# axiom_beta_plugin_module_1xUSB30.net
KiCad netlist of a schematic drawn in EAGLE
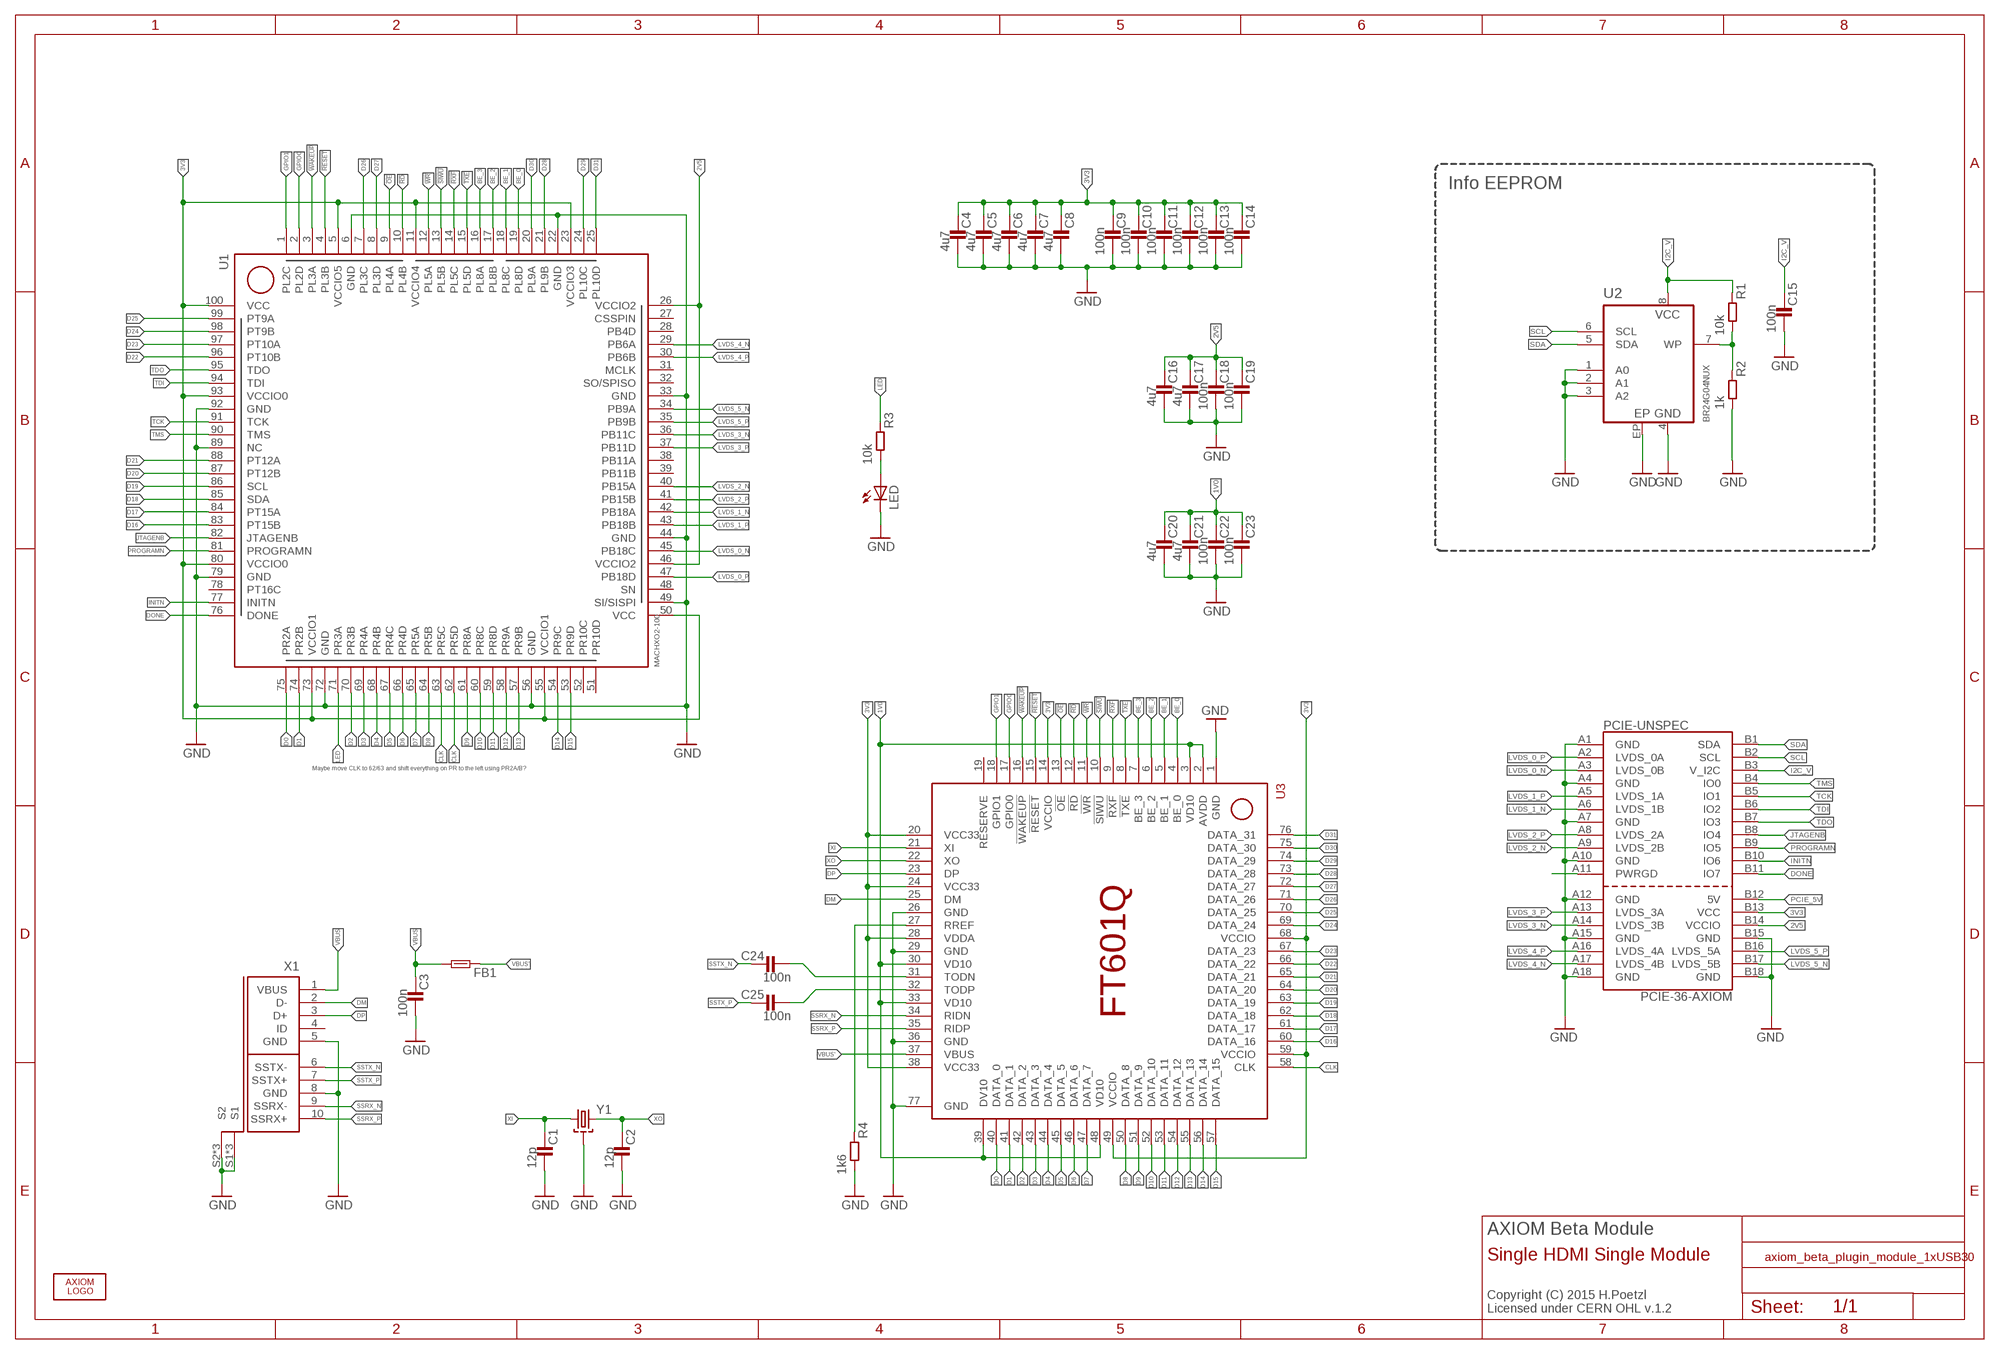
[diagram p0: schematic, sheet 1]

(export (version "E")
  (design (tool "Eeschema 10.0.6"))
  (components
    (comp (ref "C1")
      (value "12p")
      (footprint "eagle-import:0402-C")
      (libsource (lib "eagle-import") (part "C0402-C"))
    )
    (comp (ref "C2")
      (value "12p")
      (footprint "eagle-import:0402-C")
      (libsource (lib "eagle-import") (part "C0402-C"))
    )
    (comp (ref "C3")
      (value "100n")
      (footprint "eagle-import:0402-C")
      (libsource (lib "eagle-import") (part "C0402-C"))
    )
    (comp (ref "C4")
      (value "4u7")
      (footprint "eagle-import:0402-C")
      (libsource (lib "eagle-import") (part "C0402-C"))
    )
    (comp (ref "C5")
      (value "4u7")
      (footprint "eagle-import:0402-C")
      (libsource (lib "eagle-import") (part "C0402-C"))
    )
    (comp (ref "C6")
      (value "4u7")
      (footprint "eagle-import:0402-C")
      (libsource (lib "eagle-import") (part "C0402-C"))
    )
    (comp (ref "C7")
      (value "4u7")
      (footprint "eagle-import:0402-C")
      (libsource (lib "eagle-import") (part "C0402-C"))
    )
    (comp (ref "C8")
      (value "4u7")
      (footprint "eagle-import:0402-C")
      (libsource (lib "eagle-import") (part "C0402-C"))
    )
    (comp (ref "C9")
      (value "100n")
      (footprint "eagle-import:0402-C")
      (libsource (lib "eagle-import") (part "C0402-C"))
    )
    (comp (ref "C10")
      (value "100n")
      (footprint "eagle-import:0402-C")
      (libsource (lib "eagle-import") (part "C0402-C"))
    )
    (comp (ref "C11")
      (value "100n")
      (footprint "eagle-import:0402-C")
      (libsource (lib "eagle-import") (part "C0402-C"))
    )
    (comp (ref "C12")
      (value "100n")
      (footprint "eagle-import:0402-C")
      (libsource (lib "eagle-import") (part "C0402-C"))
    )
    (comp (ref "C13")
      (value "100n")
      (footprint "eagle-import:0402-C")
      (libsource (lib "eagle-import") (part "C0402-C"))
    )
    (comp (ref "C14")
      (value "100n")
      (footprint "eagle-import:0402-C")
      (libsource (lib "eagle-import") (part "C0402-C"))
    )
    (comp (ref "C15")
      (value "100n")
      (footprint "eagle-import:0402-C")
      (libsource (lib "eagle-import") (part "C0402-C"))
    )
    (comp (ref "C16")
      (value "4u7")
      (footprint "eagle-import:0402-C")
      (libsource (lib "eagle-import") (part "C0402-C"))
    )
    (comp (ref "C17")
      (value "4u7")
      (footprint "eagle-import:0402-C")
      (libsource (lib "eagle-import") (part "C0402-C"))
    )
    (comp (ref "C18")
      (value "100n")
      (footprint "eagle-import:0402-C")
      (libsource (lib "eagle-import") (part "C0402-C"))
    )
    (comp (ref "C19")
      (value "100n")
      (footprint "eagle-import:0402-C")
      (libsource (lib "eagle-import") (part "C0402-C"))
    )
    (comp (ref "C20")
      (value "4u7")
      (footprint "eagle-import:0402-C")
      (libsource (lib "eagle-import") (part "C0402-C"))
    )
    (comp (ref "C21")
      (value "4u7")
      (footprint "eagle-import:0402-C")
      (libsource (lib "eagle-import") (part "C0402-C"))
    )
    (comp (ref "C22")
      (value "100n")
      (footprint "eagle-import:0402-C")
      (libsource (lib "eagle-import") (part "C0402-C"))
    )
    (comp (ref "C23")
      (value "100n")
      (footprint "eagle-import:0402-C")
      (libsource (lib "eagle-import") (part "C0402-C"))
    )
    (comp (ref "C24")
      (value "100n")
      (footprint "eagle-import:0201-C")
      (libsource (lib "eagle-import") (part "C0201-C"))
    )
    (comp (ref "C25")
      (value "100n")
      (footprint "eagle-import:0201-C")
      (libsource (lib "eagle-import") (part "C0201-C"))
    )
    (comp (ref "FB1")
      (value "FB0402-C")
      (footprint "eagle-import:0402-C")
      (libsource (lib "eagle-import") (part "FB0402-C"))
    )
    (comp (ref "LED")
      (value "LED")
      (footprint "eagle-import:CHIPLED_0603")
      (libsource (lib "eagle-import") (part "LED"))
    )
    (comp (ref "PCIE-UNSPEC")
      (value "PCIE-36-AXIOM")
      (footprint "eagle-import:PCIE-36-AXIOM")
      (libsource (lib "eagle-import") (part "PCIE-36-AXIOM"))
    )
    (comp (ref "R1")
      (value "10k")
      (footprint "eagle-import:0402-C")
      (libsource (lib "eagle-import") (part "R0402-C"))
    )
    (comp (ref "R2")
      (value "1k")
      (footprint "eagle-import:0402-C")
      (libsource (lib "eagle-import") (part "R0402-C"))
    )
    (comp (ref "R3")
      (value "10k")
      (footprint "eagle-import:0402-B")
      (libsource (lib "eagle-import") (part "R0402-B"))
    )
    (comp (ref "R4")
      (value "1k6")
      (footprint "eagle-import:0201-C")
      (libsource (lib "eagle-import") (part "R0201-C"))
    )
    (comp (ref "U$")
      (value "AXIOM_LOGO328X50")
      (footprint "eagle-import:AXIOM_LOGO_328X50")
      (libsource (lib "eagle-import") (part "AXIOM_LOGO328X50"))
    )
    (comp (ref "U1")
      (value "MACHXO2-100")
      (footprint "eagle-import:MACHXO2-100TQFP")
      (libsource (lib "eagle-import") (part "MACHXO2-100"))
    )
    (comp (ref "U2")
      (value "BR24G04NUX")
      (footprint "eagle-import:DFN200X300X100-9N")
      (libsource (lib "eagle-import") (part "BR24G04NUX"))
    )
    (comp (ref "U3")
      (value "FT601QQFN76")
      (footprint "eagle-import:QFN76")
      (libsource (lib "eagle-import") (part "FT601QQFN76"))
    )
    (comp (ref "X1")
      (value "10_USB_3.0_2S-SMT")
      (footprint "eagle-import:MICRO-B-30-H-SMT")
      (libsource (lib "eagle-import") (part "10_USB_3.0_2S-SMT"))
    )
    (comp (ref "Y1")
      (value "SMD-4P-2G-2.0X1.6")
      (footprint "eagle-import:2.0X1.6")
      (libsource (lib "eagle-import") (part "SMD-4P-2G-2.0X1.6"))
    )
  )
  (nets
    (net (code "1") (name "/~{OE}") (class "Default")
      (node (ref "U1") (pin "9") (pinfunction "PL4A_9") (pintype "bidirectional"))
      (node (ref "U3") (pin "13") (pinfunction "~{OE}_13") (pintype "input"))
    )
    (net (code "2") (name "/~{RD}") (class "Default")
      (node (ref "U1") (pin "10") (pinfunction "PL4B_10") (pintype "bidirectional"))
      (node (ref "U3") (pin "12") (pinfunction "~{RD}_12") (pintype "input"))
    )
    (net (code "3") (name "/~{RESET}") (class "Default")
      (node (ref "U1") (pin "4") (pinfunction "PL3B_4") (pintype "bidirectional"))
      (node (ref "U3") (pin "15") (pinfunction "~{RESET}_15") (pintype "input"))
    )
    (net (code "4") (name "/~{RXF}") (class "Default")
      (node (ref "U1") (pin "14") (pinfunction "PL5C_14") (pintype "bidirectional"))
      (node (ref "U3") (pin "9") (pinfunction "~{RXF}_9") (pintype "output"))
    )
    (net (code "5") (name "/~{SIWU}") (class "Default")
      (node (ref "U1") (pin "13") (pinfunction "PL5B_13") (pintype "bidirectional"))
      (node (ref "U3") (pin "10") (pinfunction "~{SIWU}_10") (pintype "input"))
    )
    (net (code "6") (name "/~{TXE}") (class "Default")
      (node (ref "U1") (pin "15") (pinfunction "PL5D_15") (pintype "bidirectional"))
      (node (ref "U3") (pin "8") (pinfunction "~{TXE}_8") (pintype "output"))
    )
    (net (code "7") (name "/~{WAKEUP}") (class "Default")
      (node (ref "U1") (pin "3") (pinfunction "PL3A_3") (pintype "bidirectional"))
      (node (ref "U3") (pin "16") (pinfunction "~{WAKEUP}_16") (pintype "bidirectional"))
    )
    (net (code "8") (name "/~{WR}") (class "Default")
      (node (ref "U1") (pin "12") (pinfunction "PL5A_12") (pintype "bidirectional"))
      (node (ref "U3") (pin "11") (pinfunction "~{WR}_11") (pintype "input"))
    )
    (net (code "9") (name "1V0") (class "Default")
      (node (ref "C20") (pin "1") (pinfunction "1_1") (pintype "passive"))
      (node (ref "C21") (pin "1") (pinfunction "1_1") (pintype "passive"))
      (node (ref "C22") (pin "1") (pinfunction "1_1") (pintype "passive"))
      (node (ref "C23") (pin "1") (pinfunction "1_1") (pintype "passive"))
      (node (ref "U3") (pin "2") (pinfunction "AVDD_2") (pintype "power_in"))
      (node (ref "U3") (pin "3") (pinfunction "VD10_3") (pintype "power_in"))
      (node (ref "U3") (pin "30") (pinfunction "VD10_30") (pintype "power_in"))
      (node (ref "U3") (pin "33") (pinfunction "VD10_33") (pintype "power_in"))
      (node (ref "U3") (pin "39") (pinfunction "DV10_39") (pintype "power_in"))
      (node (ref "U3") (pin "48") (pinfunction "VD10_48") (pintype "power_in"))
    )
    (net (code "10") (name "2V5") (class "Default")
      (node (ref "C16") (pin "1") (pinfunction "1_1") (pintype "passive"))
      (node (ref "C17") (pin "1") (pinfunction "1_1") (pintype "passive"))
      (node (ref "C18") (pin "1") (pinfunction "1_1") (pintype "passive"))
      (node (ref "C19") (pin "1") (pinfunction "1_1") (pintype "passive"))
      (node (ref "PCIE-UNSPEC") (pin "B14") (pinfunction "VCCIO_B14") (pintype "passive"))
      (node (ref "U1") (pin "26") (pinfunction "VCCIO2_26") (pintype "power_in"))
      (node (ref "U1") (pin "46") (pinfunction "VCCIO2_46") (pintype "power_in"))
    )
    (net (code "11") (name "3V3") (class "Default")
      (node (ref "C10") (pin "1") (pinfunction "1_1") (pintype "passive"))
      (node (ref "C11") (pin "1") (pinfunction "1_1") (pintype "passive"))
      (node (ref "C12") (pin "1") (pinfunction "1_1") (pintype "passive"))
      (node (ref "C13") (pin "1") (pinfunction "1_1") (pintype "passive"))
      (node (ref "C14") (pin "1") (pinfunction "1_1") (pintype "passive"))
      (node (ref "C4") (pin "1") (pinfunction "1_1") (pintype "passive"))
      (node (ref "C5") (pin "1") (pinfunction "1_1") (pintype "passive"))
      (node (ref "C6") (pin "1") (pinfunction "1_1") (pintype "passive"))
      (node (ref "C7") (pin "1") (pinfunction "1_1") (pintype "passive"))
      (node (ref "C8") (pin "1") (pinfunction "1_1") (pintype "passive"))
      (node (ref "C9") (pin "1") (pinfunction "1_1") (pintype "passive"))
      (node (ref "PCIE-UNSPEC") (pin "B13") (pinfunction "VCC_B13") (pintype "passive"))
      (node (ref "U1") (pin "100") (pinfunction "VCC_100") (pintype "power_in"))
      (node (ref "U1") (pin "11") (pinfunction "VCCIO4_11") (pintype "power_in"))
      (node (ref "U1") (pin "23") (pinfunction "VCCIO3_23") (pintype "power_in"))
      (node (ref "U1") (pin "5") (pinfunction "VCCIO5_5") (pintype "power_in"))
      (node (ref "U1") (pin "50") (pinfunction "VCC_50") (pintype "power_in"))
      (node (ref "U1") (pin "55") (pinfunction "VCCIO1_55") (pintype "power_in"))
      (node (ref "U1") (pin "73") (pinfunction "VCCIO1_73") (pintype "power_in"))
      (node (ref "U1") (pin "80") (pinfunction "VCCIO0_80") (pintype "power_in"))
      (node (ref "U1") (pin "93") (pinfunction "VCCIO0_93") (pintype "power_in"))
      (node (ref "U3") (pin "14") (pinfunction "VCCIO_14") (pintype "power_in"))
      (node (ref "U3") (pin "20") (pinfunction "VCC33_20") (pintype "power_in"))
      (node (ref "U3") (pin "24") (pinfunction "VCC33_24") (pintype "power_in"))
      (node (ref "U3") (pin "28") (pinfunction "VDDA_28") (pintype "bidirectional"))
      (node (ref "U3") (pin "38") (pinfunction "VCC33_38") (pintype "power_in"))
      (node (ref "U3") (pin "49") (pinfunction "VCCIO_49") (pintype "power_in"))
      (node (ref "U3") (pin "59") (pinfunction "VCCIO_59") (pintype "power_in"))
      (node (ref "U3") (pin "68") (pinfunction "VCCIO_68") (pintype "power_in"))
    )
    (net (code "12") (name "BE_0") (class "Default")
      (node (ref "U1") (pin "19") (pinfunction "PL8D_19") (pintype "bidirectional"))
      (node (ref "U3") (pin "4") (pinfunction "BE_0_4") (pintype "bidirectional"))
    )
    (net (code "13") (name "BE_1") (class "Default")
      (node (ref "U1") (pin "18") (pinfunction "PL8C_18") (pintype "bidirectional"))
      (node (ref "U3") (pin "5") (pinfunction "BE_1_5") (pintype "bidirectional"))
    )
    (net (code "14") (name "BE_2") (class "Default")
      (node (ref "U1") (pin "17") (pinfunction "PL8B_17") (pintype "bidirectional"))
      (node (ref "U3") (pin "6") (pinfunction "BE_2_6") (pintype "bidirectional"))
    )
    (net (code "15") (name "BE_3") (class "Default")
      (node (ref "U1") (pin "16") (pinfunction "PL8A_16") (pintype "bidirectional"))
      (node (ref "U3") (pin "7") (pinfunction "BE_3_7") (pintype "bidirectional"))
    )
    (net (code "16") (name "CLK") (class "Default")
      (node (ref "U1") (pin "62") (pinfunction "PR5D_62") (pintype "bidirectional"))
      (node (ref "U1") (pin "63") (pinfunction "PR5C_63") (pintype "bidirectional"))
      (node (ref "U3") (pin "58") (pinfunction "CLK_58") (pintype "output"))
    )
    (net (code "17") (name "D0") (class "Default")
      (node (ref "U1") (pin "75") (pinfunction "PR2A_75") (pintype "bidirectional"))
      (node (ref "U3") (pin "40") (pinfunction "DATA_0_40") (pintype "bidirectional"))
    )
    (net (code "18") (name "D1") (class "Default")
      (node (ref "U1") (pin "74") (pinfunction "PR2B_74") (pintype "bidirectional"))
      (node (ref "U3") (pin "41") (pinfunction "DATA_1_41") (pintype "bidirectional"))
    )
    (net (code "19") (name "D2") (class "Default")
      (node (ref "U1") (pin "70") (pinfunction "PR3B_70") (pintype "bidirectional"))
      (node (ref "U3") (pin "42") (pinfunction "DATA_2_42") (pintype "bidirectional"))
    )
    (net (code "20") (name "D3") (class "Default")
      (node (ref "U1") (pin "69") (pinfunction "PR4A_69") (pintype "bidirectional"))
      (node (ref "U3") (pin "43") (pinfunction "DATA_3_43") (pintype "bidirectional"))
    )
    (net (code "21") (name "D4") (class "Default")
      (node (ref "U1") (pin "68") (pinfunction "PR4B_68") (pintype "bidirectional"))
      (node (ref "U3") (pin "44") (pinfunction "DATA_4_44") (pintype "bidirectional"))
    )
    (net (code "22") (name "D5") (class "Default")
      (node (ref "U1") (pin "67") (pinfunction "PR4C_67") (pintype "bidirectional"))
      (node (ref "U3") (pin "45") (pinfunction "DATA_5_45") (pintype "bidirectional"))
    )
    (net (code "23") (name "D6") (class "Default")
      (node (ref "U1") (pin "66") (pinfunction "PR4D_66") (pintype "bidirectional"))
      (node (ref "U3") (pin "46") (pinfunction "DATA_6_46") (pintype "bidirectional"))
    )
    (net (code "24") (name "D7") (class "Default")
      (node (ref "U1") (pin "65") (pinfunction "PR5A_65") (pintype "bidirectional"))
      (node (ref "U3") (pin "47") (pinfunction "DATA_7_47") (pintype "bidirectional"))
    )
    (net (code "25") (name "D8") (class "Default")
      (node (ref "U1") (pin "64") (pinfunction "PR5B_64") (pintype "bidirectional"))
      (node (ref "U3") (pin "50") (pinfunction "DATA_8_50") (pintype "bidirectional"))
    )
    (net (code "26") (name "D9") (class "Default")
      (node (ref "U1") (pin "61") (pinfunction "PR8A_61") (pintype "bidirectional"))
      (node (ref "U3") (pin "51") (pinfunction "DATA_9_51") (pintype "bidirectional"))
    )
    (net (code "27") (name "D10") (class "Default")
      (node (ref "U1") (pin "60") (pinfunction "PR8C_60") (pintype "bidirectional"))
      (node (ref "U3") (pin "52") (pinfunction "DATA_10_52") (pintype "bidirectional"))
    )
    (net (code "28") (name "D11") (class "Default")
      (node (ref "U1") (pin "59") (pinfunction "PR8D_59") (pintype "bidirectional"))
      (node (ref "U3") (pin "53") (pinfunction "DATA_11_53") (pintype "bidirectional"))
    )
    (net (code "29") (name "D12") (class "Default")
      (node (ref "U1") (pin "58") (pinfunction "PR9A_58") (pintype "bidirectional"))
      (node (ref "U3") (pin "54") (pinfunction "DATA_12_54") (pintype "bidirectional"))
    )
    (net (code "30") (name "D13") (class "Default")
      (node (ref "U1") (pin "57") (pinfunction "PR9B_57") (pintype "bidirectional"))
      (node (ref "U3") (pin "55") (pinfunction "DATA_13_55") (pintype "bidirectional"))
    )
    (net (code "31") (name "D14") (class "Default")
      (node (ref "U1") (pin "54") (pinfunction "PR9C_54") (pintype "bidirectional"))
      (node (ref "U3") (pin "56") (pinfunction "DATA_14_56") (pintype "bidirectional"))
    )
    (net (code "32") (name "D15") (class "Default")
      (node (ref "U1") (pin "53") (pinfunction "PR9D_53") (pintype "bidirectional"))
      (node (ref "U3") (pin "57") (pinfunction "DATA_15_57") (pintype "bidirectional"))
    )
    (net (code "33") (name "D16") (class "Default")
      (node (ref "U1") (pin "83") (pinfunction "PT15B_83") (pintype "bidirectional"))
      (node (ref "U3") (pin "60") (pinfunction "DATA_16_60") (pintype "bidirectional"))
    )
    (net (code "34") (name "D17") (class "Default")
      (node (ref "U1") (pin "84") (pinfunction "PT15A_84") (pintype "bidirectional"))
      (node (ref "U3") (pin "61") (pinfunction "DATA_17_61") (pintype "bidirectional"))
    )
    (net (code "35") (name "D18") (class "Default")
      (node (ref "U1") (pin "85") (pinfunction "SDA_85") (pintype "bidirectional"))
      (node (ref "U3") (pin "62") (pinfunction "DATA_18_62") (pintype "bidirectional"))
    )
    (net (code "36") (name "D19") (class "Default")
      (node (ref "U1") (pin "86") (pinfunction "SCL_86") (pintype "bidirectional"))
      (node (ref "U3") (pin "63") (pinfunction "DATA_19_63") (pintype "bidirectional"))
    )
    (net (code "37") (name "D20") (class "Default")
      (node (ref "U1") (pin "87") (pinfunction "PT12B_87") (pintype "bidirectional"))
      (node (ref "U3") (pin "64") (pinfunction "DATA_20_64") (pintype "bidirectional"))
    )
    (net (code "38") (name "D21") (class "Default")
      (node (ref "U1") (pin "88") (pinfunction "PT12A_88") (pintype "bidirectional"))
      (node (ref "U3") (pin "65") (pinfunction "DATA_21_65") (pintype "bidirectional"))
    )
    (net (code "39") (name "D22") (class "Default")
      (node (ref "U1") (pin "96") (pinfunction "PT10B_96") (pintype "bidirectional"))
      (node (ref "U3") (pin "66") (pinfunction "DATA_22_66") (pintype "bidirectional"))
    )
    (net (code "40") (name "D23") (class "Default")
      (node (ref "U1") (pin "97") (pinfunction "PT10A_97") (pintype "bidirectional"))
      (node (ref "U3") (pin "67") (pinfunction "DATA_23_67") (pintype "bidirectional"))
    )
    (net (code "41") (name "D24") (class "Default")
      (node (ref "U1") (pin "98") (pinfunction "PT9B_98") (pintype "bidirectional"))
      (node (ref "U3") (pin "69") (pinfunction "DATA_24_69") (pintype "bidirectional"))
    )
    (net (code "42") (name "D25") (class "Default")
      (node (ref "U1") (pin "99") (pinfunction "PT9A_99") (pintype "bidirectional"))
      (node (ref "U3") (pin "70") (pinfunction "DATA_25_70") (pintype "bidirectional"))
    )
    (net (code "43") (name "D26") (class "Default")
      (node (ref "U1") (pin "7") (pinfunction "PL3C_7") (pintype "bidirectional"))
      (node (ref "U3") (pin "71") (pinfunction "DATA_26_71") (pintype "bidirectional"))
    )
    (net (code "44") (name "D27") (class "Default")
      (node (ref "U1") (pin "8") (pinfunction "PL3D_8") (pintype "bidirectional"))
      (node (ref "U3") (pin "72") (pinfunction "DATA_27_72") (pintype "bidirectional"))
    )
    (net (code "45") (name "D28") (class "Default")
      (node (ref "U1") (pin "21") (pinfunction "PL9B_21") (pintype "bidirectional"))
      (node (ref "U3") (pin "73") (pinfunction "DATA_28_73") (pintype "bidirectional"))
    )
    (net (code "46") (name "D29") (class "Default")
      (node (ref "U1") (pin "24") (pinfunction "PL10C_24") (pintype "bidirectional"))
      (node (ref "U3") (pin "74") (pinfunction "DATA_29_74") (pintype "bidirectional"))
    )
    (net (code "47") (name "D30") (class "Default")
      (node (ref "U1") (pin "20") (pinfunction "PL9A_20") (pintype "bidirectional"))
      (node (ref "U3") (pin "75") (pinfunction "DATA_30_75") (pintype "bidirectional"))
    )
    (net (code "48") (name "D31") (class "Default")
      (node (ref "U1") (pin "25") (pinfunction "PL10D_25") (pintype "bidirectional"))
      (node (ref "U3") (pin "76") (pinfunction "DATA_31_76") (pintype "bidirectional"))
    )
    (net (code "49") (name "DM") (class "Default")
      (node (ref "U3") (pin "25") (pinfunction "DM_25") (pintype "bidirectional"))
      (node (ref "X1") (pin "2") (pinfunction "D-_2") (pintype "passive"))
    )
    (net (code "50") (name "DONE") (class "Default")
      (node (ref "PCIE-UNSPEC") (pin "B11") (pinfunction "IO7_B11") (pintype "passive"))
      (node (ref "U1") (pin "76") (pinfunction "DONE_76") (pintype "bidirectional"))
    )
    (net (code "51") (name "DP") (class "Default")
      (node (ref "U3") (pin "23") (pinfunction "DP_23") (pintype "bidirectional"))
      (node (ref "X1") (pin "3") (pinfunction "D+_3") (pintype "passive"))
    )
    (net (code "52") (name "GND") (class "Default")
      (node (ref "C1") (pin "2") (pinfunction "2_2") (pintype "passive"))
      (node (ref "C10") (pin "2") (pinfunction "2_2") (pintype "passive"))
      (node (ref "C11") (pin "2") (pinfunction "2_2") (pintype "passive"))
      (node (ref "C12") (pin "2") (pinfunction "2_2") (pintype "passive"))
      (node (ref "C13") (pin "2") (pinfunction "2_2") (pintype "passive"))
      (node (ref "C14") (pin "2") (pinfunction "2_2") (pintype "passive"))
      (node (ref "C15") (pin "2") (pinfunction "2_2") (pintype "passive"))
      (node (ref "C16") (pin "2") (pinfunction "2_2") (pintype "passive"))
      (node (ref "C17") (pin "2") (pinfunction "2_2") (pintype "passive"))
      (node (ref "C18") (pin "2") (pinfunction "2_2") (pintype "passive"))
      (node (ref "C19") (pin "2") (pinfunction "2_2") (pintype "passive"))
      (node (ref "C2") (pin "2") (pinfunction "2_2") (pintype "passive"))
      (node (ref "C20") (pin "2") (pinfunction "2_2") (pintype "passive"))
      (node (ref "C21") (pin "2") (pinfunction "2_2") (pintype "passive"))
      (node (ref "C22") (pin "2") (pinfunction "2_2") (pintype "passive"))
      (node (ref "C23") (pin "2") (pinfunction "2_2") (pintype "passive"))
      (node (ref "C3") (pin "2") (pinfunction "2_2") (pintype "passive"))
      (node (ref "C4") (pin "2") (pinfunction "2_2") (pintype "passive"))
      (node (ref "C5") (pin "2") (pinfunction "2_2") (pintype "passive"))
      (node (ref "C6") (pin "2") (pinfunction "2_2") (pintype "passive"))
      (node (ref "C7") (pin "2") (pinfunction "2_2") (pintype "passive"))
      (node (ref "C8") (pin "2") (pinfunction "2_2") (pintype "passive"))
      (node (ref "C9") (pin "2") (pinfunction "2_2") (pintype "passive"))
      (node (ref "LED") (pin "C") (pinfunction "C_C") (pintype "passive"))
      (node (ref "PCIE-UNSPEC") (pin "A1") (pinfunction "GND_A1") (pintype "passive"))
      (node (ref "PCIE-UNSPEC") (pin "A10") (pinfunction "GND_A10") (pintype "passive"))
      (node (ref "PCIE-UNSPEC") (pin "A12") (pinfunction "GND_A12") (pintype "passive"))
      (node (ref "PCIE-UNSPEC") (pin "A15") (pinfunction "GND_A15") (pintype "passive"))
      (node (ref "PCIE-UNSPEC") (pin "A18") (pinfunction "GND_A18") (pintype "passive"))
      (node (ref "PCIE-UNSPEC") (pin "A4") (pinfunction "GND_A4") (pintype "passive"))
      (node (ref "PCIE-UNSPEC") (pin "A7") (pinfunction "GND_A7") (pintype "passive"))
      (node (ref "PCIE-UNSPEC") (pin "B15") (pinfunction "GND_B15") (pintype "passive"))
      (node (ref "PCIE-UNSPEC") (pin "B18") (pinfunction "GND_B18") (pintype "passive"))
      (node (ref "R2") (pin "2") (pinfunction "2_2") (pintype "passive"))
      (node (ref "R4") (pin "2") (pinfunction "2_2") (pintype "passive"))
      (node (ref "U1") (pin "22") (pinfunction "GND_22") (pintype "power_in"))
      (node (ref "U1") (pin "33") (pinfunction "GND_33") (pintype "power_in"))
      (node (ref "U1") (pin "44") (pinfunction "GND_44") (pintype "power_in"))
      (node (ref "U1") (pin "49") (pinfunction "SI/SISPI_49") (pintype "bidirectional"))
      (node (ref "U1") (pin "56") (pinfunction "GND_56") (pintype "power_in"))
      (node (ref "U1") (pin "6") (pinfunction "GND_6") (pintype "power_in"))
      (node (ref "U1") (pin "72") (pinfunction "GND_72") (pintype "power_in"))
      (node (ref "U1") (pin "79") (pinfunction "GND_79") (pintype "power_in"))
      (node (ref "U1") (pin "89") (pinfunction "NC_89") (pintype "bidirectional"))
      (node (ref "U1") (pin "92") (pinfunction "GND_92") (pintype "power_in"))
      (node (ref "U2") (pin "1") (pinfunction "A0_1") (pintype "input"))
      (node (ref "U2") (pin "2") (pinfunction "A1_2") (pintype "input"))
      (node (ref "U2") (pin "3") (pinfunction "A2_3") (pintype "input"))
      (node (ref "U2") (pin "4") (pinfunction "GND_4") (pintype "passive"))
      (node (ref "U2") (pin "EP") (pinfunction "EP_EP") (pintype "passive"))
      (node (ref "U3") (pin "1") (pinfunction "GND_1") (pintype "power_in"))
      (node (ref "U3") (pin "26") (pinfunction "GND_26") (pintype "power_in"))
      (node (ref "U3") (pin "29") (pinfunction "GND_29") (pintype "power_in"))
      (node (ref "U3") (pin "36") (pinfunction "GND_36") (pintype "power_in"))
      (node (ref "U3") (pin "77") (pinfunction "GND_77") (pintype "power_in"))
      (node (ref "X1") (pin "5") (pinfunction "GND_5") (pintype "passive"))
      (node (ref "X1") (pin "8") (pinfunction "GND_8") (pintype "passive"))
      (node (ref "X1") (pin "S1") (pinfunction "S1_S1") (pintype "passive"))
      (node (ref "X1") (pin "S2") (pinfunction "S2_S2") (pintype "passive"))
      (node (ref "X1") (pin "Z1") (pinfunction "S1_Z1") (pintype "passive"))
      (node (ref "X1") (pin "Z2") (pinfunction "S1_Z2") (pintype "passive"))
      (node (ref "X1") (pin "Z3") (pinfunction "S2_Z3") (pintype "passive"))
      (node (ref "X1") (pin "Z4") (pinfunction "S2_Z4") (pintype "passive"))
      (node (ref "Y1") (pin "2") (pinfunction "GND_2") (pintype "power_in"))
      (node (ref "Y1") (pin "4") (pinfunction "GND_4") (pintype "power_in"))
    )
    (net (code "53") (name "GPIO0") (class "Default")
      (node (ref "U1") (pin "2") (pinfunction "PL2D_2") (pintype "bidirectional"))
      (node (ref "U3") (pin "17") (pinfunction "GPIO0_17") (pintype "bidirectional"))
    )
    (net (code "54") (name "GPIO1") (class "Default")
      (node (ref "U1") (pin "1") (pinfunction "PL2C_1") (pintype "bidirectional"))
      (node (ref "U3") (pin "18") (pinfunction "GPIO1_18") (pintype "bidirectional"))
    )
    (net (code "55") (name "I2C_V") (class "Default")
      (node (ref "C15") (pin "1") (pinfunction "1_1") (pintype "passive"))
      (node (ref "PCIE-UNSPEC") (pin "B3") (pinfunction "V_I2C_B3") (pintype "passive"))
      (node (ref "R1") (pin "1") (pinfunction "1_1") (pintype "passive"))
      (node (ref "U2") (pin "8") (pinfunction "VCC_8") (pintype "power_in"))
    )
    (net (code "56") (name "INITN") (class "Default")
      (node (ref "PCIE-UNSPEC") (pin "B10") (pinfunction "IO6_B10") (pintype "passive"))
      (node (ref "U1") (pin "77") (pinfunction "INITN_77") (pintype "bidirectional"))
    )
    (net (code "57") (name "JTAGENB") (class "Default")
      (node (ref "PCIE-UNSPEC") (pin "B8") (pinfunction "IO4_B8") (pintype "passive"))
      (node (ref "U1") (pin "82") (pinfunction "JTAGENB_82") (pintype "bidirectional"))
    )
    (net (code "58") (name "LED") (class "Default")
      (node (ref "R3") (pin "1") (pinfunction "1_1") (pintype "passive"))
      (node (ref "U1") (pin "71") (pinfunction "PR3A_71") (pintype "bidirectional"))
    )
    (net (code "59") (name "LVDS_0_N") (class "Default")
      (node (ref "PCIE-UNSPEC") (pin "A3") (pinfunction "LVDS_0B_A3") (pintype "passive"))
      (node (ref "U1") (pin "45") (pinfunction "PB18C_45") (pintype "bidirectional"))
    )
    (net (code "60") (name "LVDS_0_P") (class "Default")
      (node (ref "PCIE-UNSPEC") (pin "A2") (pinfunction "LVDS_0A_A2") (pintype "passive"))
      (node (ref "U1") (pin "47") (pinfunction "PB18D_47") (pintype "bidirectional"))
    )
    (net (code "61") (name "LVDS_1_N") (class "Default")
      (node (ref "PCIE-UNSPEC") (pin "A6") (pinfunction "LVDS_1B_A6") (pintype "passive"))
      (node (ref "U1") (pin "42") (pinfunction "PB18A_42") (pintype "bidirectional"))
    )
    (net (code "62") (name "LVDS_1_P") (class "Default")
      (node (ref "PCIE-UNSPEC") (pin "A5") (pinfunction "LVDS_1A_A5") (pintype "passive"))
      (node (ref "U1") (pin "43") (pinfunction "PB18B_43") (pintype "bidirectional"))
    )
    (net (code "63") (name "LVDS_2_N") (class "Default")
      (node (ref "PCIE-UNSPEC") (pin "A9") (pinfunction "LVDS_2B_A9") (pintype "passive"))
      (node (ref "U1") (pin "40") (pinfunction "PB15A_40") (pintype "bidirectional"))
    )
    (net (code "64") (name "LVDS_2_P") (class "Default")
      (node (ref "PCIE-UNSPEC") (pin "A8") (pinfunction "LVDS_2A_A8") (pintype "passive"))
      (node (ref "U1") (pin "41") (pinfunction "PB15B_41") (pintype "bidirectional"))
    )
    (net (code "65") (name "LVDS_3_N") (class "Default")
      (node (ref "PCIE-UNSPEC") (pin "A14") (pinfunction "LVDS_3B_A14") (pintype "passive"))
      (node (ref "U1") (pin "36") (pinfunction "PB11C_36") (pintype "bidirectional"))
    )
    (net (code "66") (name "LVDS_3_P") (class "Default")
      (node (ref "PCIE-UNSPEC") (pin "A13") (pinfunction "LVDS_3A_A13") (pintype "passive"))
      (node (ref "U1") (pin "37") (pinfunction "PB11D_37") (pintype "bidirectional"))
    )
    (net (code "67") (name "LVDS_4_N") (class "Default")
      (node (ref "PCIE-UNSPEC") (pin "A17") (pinfunction "LVDS_4B_A17") (pintype "passive"))
      (node (ref "U1") (pin "29") (pinfunction "PB6A_29") (pintype "bidirectional"))
    )
    (net (code "68") (name "LVDS_4_P") (class "Default")
      (node (ref "PCIE-UNSPEC") (pin "A16") (pinfunction "LVDS_4A_A16") (pintype "passive"))
      (node (ref "U1") (pin "30") (pinfunction "PB6B_30") (pintype "bidirectional"))
    )
    (net (code "69") (name "LVDS_5_N") (class "Default")
      (node (ref "PCIE-UNSPEC") (pin "B17") (pinfunction "LVDS_5B_B17") (pintype "passive"))
      (node (ref "U1") (pin "34") (pinfunction "PB9A_34") (pintype "bidirectional"))
    )
    (net (code "70") (name "LVDS_5_P") (class "Default")
      (node (ref "PCIE-UNSPEC") (pin "B16") (pinfunction "LVDS_5A_B16") (pintype "passive"))
      (node (ref "U1") (pin "35") (pinfunction "PB9B_35") (pintype "bidirectional"))
    )
    (net (code "71") (name "Net-(LED-PadA)") (class "Default")
      (node (ref "LED") (pin "A") (pinfunction "A_A") (pintype "passive"))
      (node (ref "R3") (pin "2") (pinfunction "2_2") (pintype "passive"))
    )
    (net (code "72") (name "Net-(U2-WP)") (class "Default")
      (node (ref "R1") (pin "2") (pinfunction "2_2") (pintype "passive"))
      (node (ref "R2") (pin "1") (pinfunction "1_1") (pintype "passive"))
      (node (ref "U2") (pin "7") (pinfunction "WP_7") (pintype "input"))
    )
    (net (code "73") (name "Net-(U3-RREF)") (class "Default")
      (node (ref "R4") (pin "1") (pinfunction "1_1") (pintype "passive"))
      (node (ref "U3") (pin "27") (pinfunction "RREF_27") (pintype "input"))
    )
    (net (code "74") (name "Net-(U3-TODN)") (class "Default")
      (node (ref "C24") (pin "2") (pinfunction "2_2") (pintype "passive"))
      (node (ref "U3") (pin "31") (pinfunction "TODN_31") (pintype "output"))
    )
    (net (code "75") (name "Net-(U3-TODP)") (class "Default")
      (node (ref "C25") (pin "2") (pinfunction "2_2") (pintype "passive"))
      (node (ref "U3") (pin "32") (pinfunction "TODP_32") (pintype "output"))
    )
    (net (code "76") (name "PCIE_5V") (class "Default")
      (node (ref "PCIE-UNSPEC") (pin "B12") (pinfunction "5V_B12") (pintype "passive"))
    )
    (net (code "77") (name "PROGRAMN") (class "Default")
      (node (ref "PCIE-UNSPEC") (pin "B9") (pinfunction "IO5_B9") (pintype "passive"))
      (node (ref "U1") (pin "81") (pinfunction "PROGRAMN_81") (pintype "bidirectional"))
    )
    (net (code "78") (name "SCL") (class "Default")
      (node (ref "PCIE-UNSPEC") (pin "B2") (pinfunction "SCL_B2") (pintype "passive"))
      (node (ref "U2") (pin "6") (pinfunction "SCL_6") (pintype "input"))
    )
    (net (code "79") (name "SDA") (class "Default")
      (node (ref "PCIE-UNSPEC") (pin "B1") (pinfunction "SDA_B1") (pintype "passive"))
      (node (ref "U2") (pin "5") (pinfunction "SDA_5") (pintype "bidirectional"))
    )
    (net (code "80") (name "SSRX_N") (class "Default")
      (node (ref "U3") (pin "34") (pinfunction "RIDN_34") (pintype "input"))
      (node (ref "X1") (pin "9") (pinfunction "SSRX-_9") (pintype "passive"))
    )
    (net (code "81") (name "SSRX_P") (class "Default")
      (node (ref "U3") (pin "35") (pinfunction "RIDP_35") (pintype "input"))
      (node (ref "X1") (pin "10") (pinfunction "SSRX+_10") (pintype "passive"))
    )
    (net (code "82") (name "SSTX_N") (class "Default")
      (node (ref "C24") (pin "1") (pinfunction "1_1") (pintype "passive"))
      (node (ref "X1") (pin "6") (pinfunction "SSTX-_6") (pintype "passive"))
    )
    (net (code "83") (name "SSTX_P") (class "Default")
      (node (ref "C25") (pin "1") (pinfunction "1_1") (pintype "passive"))
      (node (ref "X1") (pin "7") (pinfunction "SSTX+_7") (pintype "passive"))
    )
    (net (code "84") (name "TCK") (class "Default")
      (node (ref "PCIE-UNSPEC") (pin "B5") (pinfunction "IO1_B5") (pintype "passive"))
      (node (ref "U1") (pin "91") (pinfunction "TCK_91") (pintype "bidirectional"))
    )
    (net (code "85") (name "TDI") (class "Default")
      (node (ref "PCIE-UNSPEC") (pin "B6") (pinfunction "IO2_B6") (pintype "passive"))
      (node (ref "U1") (pin "94") (pinfunction "TDI_94") (pintype "bidirectional"))
    )
    (net (code "86") (name "TDO") (class "Default")
      (node (ref "PCIE-UNSPEC") (pin "B7") (pinfunction "IO3_B7") (pintype "passive"))
      (node (ref "U1") (pin "95") (pinfunction "TDO_95") (pintype "bidirectional"))
    )
    (net (code "87") (name "TMS") (class "Default")
      (node (ref "PCIE-UNSPEC") (pin "B4") (pinfunction "IO0_B4") (pintype "passive"))
      (node (ref "U1") (pin "90") (pinfunction "TMS_90") (pintype "bidirectional"))
    )
    (net (code "88") (name "VBUS") (class "Default")
      (node (ref "C3") (pin "1") (pinfunction "1_1") (pintype "passive"))
      (node (ref "FB1") (pin "2") (pinfunction "2_2") (pintype "passive"))
      (node (ref "X1") (pin "1") (pinfunction "VBUS_1") (pintype "passive"))
    )
    (net (code "89") (name "VBUS'") (class "Default")
      (node (ref "FB1") (pin "1") (pinfunction "1_1") (pintype "passive"))
      (node (ref "U3") (pin "37") (pinfunction "VBUS_37") (pintype "power_in"))
    )
    (net (code "90") (name "XI") (class "Default")
      (node (ref "C1") (pin "1") (pinfunction "1_1") (pintype "passive"))
      (node (ref "U3") (pin "21") (pinfunction "XI_21") (pintype "input"))
      (node (ref "Y1") (pin "1") (pinfunction "1_1") (pintype "passive"))
    )
    (net (code "91") (name "XO") (class "Default")
      (node (ref "C2") (pin "1") (pinfunction "1_1") (pintype "passive"))
      (node (ref "U3") (pin "22") (pinfunction "XO_22") (pintype "output"))
      (node (ref "Y1") (pin "3") (pinfunction "2_3") (pintype "passive"))
    )
    (net (code "92") (name "unconnected-(PCIE-UNSPEC-PWRGD-PadA11)") (class "Default")
      (node (ref "PCIE-UNSPEC") (pin "A11") (pinfunction "PWRGD_A11") (pintype "passive"))
    )
    (net (code "93") (name "unconnected-(U1-CSSPIN-Pad27)") (class "Default")
      (node (ref "U1") (pin "27") (pinfunction "CSSPIN_27") (pintype "bidirectional"))
    )
    (net (code "94") (name "unconnected-(U1-MCLK-Pad31)") (class "Default")
      (node (ref "U1") (pin "31") (pinfunction "MCLK_31") (pintype "bidirectional"))
    )
    (net (code "95") (name "unconnected-(U1-PB4D-Pad28)") (class "Default")
      (node (ref "U1") (pin "28") (pinfunction "PB4D_28") (pintype "bidirectional"))
    )
    (net (code "96") (name "unconnected-(U1-PB11A-Pad38)") (class "Default")
      (node (ref "U1") (pin "38") (pinfunction "PB11A_38") (pintype "bidirectional"))
    )
    (net (code "97") (name "unconnected-(U1-PB11B-Pad39)") (class "Default")
      (node (ref "U1") (pin "39") (pinfunction "PB11B_39") (pintype "bidirectional"))
    )
    (net (code "98") (name "unconnected-(U1-PR10C-Pad52)") (class "Default")
      (node (ref "U1") (pin "52") (pinfunction "PR10C_52") (pintype "bidirectional"))
    )
    (net (code "99") (name "unconnected-(U1-PR10D-Pad51)") (class "Default")
      (node (ref "U1") (pin "51") (pinfunction "PR10D_51") (pintype "bidirectional"))
    )
    (net (code "100") (name "unconnected-(U1-PT16C-Pad78)") (class "Default")
      (node (ref "U1") (pin "78") (pinfunction "PT16C_78") (pintype "bidirectional"))
    )
    (net (code "101") (name "unconnected-(U1-SN-Pad48)") (class "Default")
      (node (ref "U1") (pin "48") (pinfunction "SN_48") (pintype "bidirectional"))
    )
    (net (code "102") (name "unconnected-(U1-SO{slash}SPISO-Pad32)") (class "Default")
      (node (ref "U1") (pin "32") (pinfunction "SO/SPISO_32") (pintype "bidirectional"))
    )
    (net (code "103") (name "unconnected-(U3-RESERVE-Pad19)") (class "Default")
      (node (ref "U3") (pin "19") (pinfunction "RESERVE_19") (pintype "bidirectional"))
    )
    (net (code "104") (name "unconnected-(X1-ID-Pad4)") (class "Default")
      (node (ref "X1") (pin "4") (pinfunction "ID_4") (pintype "passive"))
    )
  )
)
